# ARMBAND.net
KiCad netlist of a schematic drawn in Altium Designer
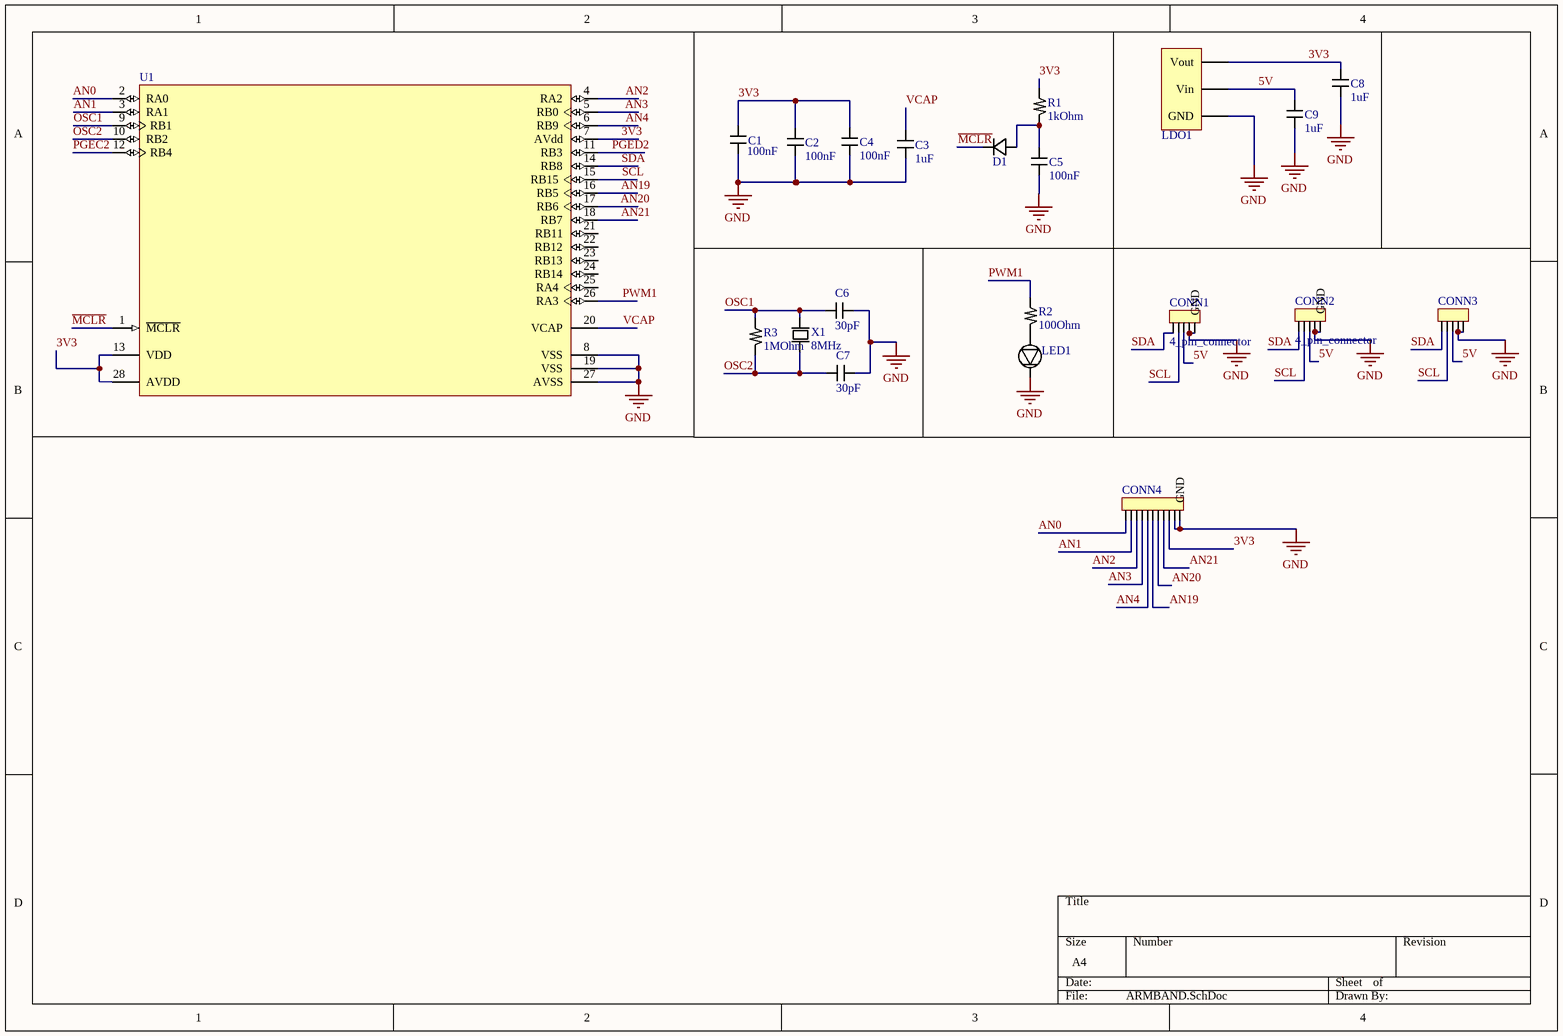
[diagram p0: ARMBAND.SchDoc]

(export (version "E")
  (design (tool "Eeschema 10.0.6"))
  (components
    (comp (ref "C1")
      (value "100nF")
      (footprint "CApacitor_1608")
      (description "SMD Capacitor")
      (libsource (lib "ARMBand_Components") (part "Capacitor_SMD"))
    )
    (comp (ref "C2")
      (value "100nF")
      (footprint "CApacitor_1608")
      (description "SMD Capacitor")
      (libsource (lib "ARMBand_Components") (part "Capacitor_SMD"))
    )
    (comp (ref "C3")
      (value "1uF")
      (footprint "Capacitor_20x12")
      (description "SMD Capacitor")
      (libsource (lib "ARMBand_Components") (part "Capacitor_SMD"))
    )
    (comp (ref "C4")
      (value "100nF")
      (footprint "CApacitor_1608")
      (description "SMD Capacitor")
      (libsource (lib "ARMBand_Components") (part "Capacitor_SMD"))
    )
    (comp (ref "C5")
      (value "100nF")
      (footprint "CApacitor_1608")
      (description "SMD Capacitor")
      (libsource (lib "ARMBand_Components") (part "Capacitor_SMD"))
    )
    (comp (ref "C6")
      (value "30pF")
      (footprint "CApacitor_1608")
      (description "SMD Capacitor")
      (libsource (lib "ARMBand_Components") (part "Capacitor_SMD"))
    )
    (comp (ref "C7")
      (value "30pF")
      (footprint "CApacitor_1608")
      (description "SMD Capacitor")
      (libsource (lib "ARMBand_Components") (part "Capacitor_SMD"))
    )
    (comp (ref "C8")
      (value "1uF")
      (footprint "Capacitor_20x12")
      (description "SMD Capacitor")
      (libsource (lib "") (part "Capacitor_SMD_1"))
    )
    (comp (ref "C9")
      (value "1uF")
      (footprint "Capacitor_20x12")
      (description "SMD Capacitor")
      (libsource (lib "") (part "Capacitor_SMD_1"))
    )
    (comp (ref "CONN1")
      (value "4_pin_connector")
      (footprint "4PIN_1MMPITCH_FFC_FCP_ZIF")
      (description "4 Pin Connector")
      (libsource (lib "") (part "4_pin_connector_1"))
    )
    (comp (ref "CONN2")
      (value "4_pin_connector")
      (footprint "4PIN_1MMPITCH_FFC_FCP_ZIF")
      (description "4 Pin Connector")
      (libsource (lib "") (part "4_pin_connector_1"))
    )
    (comp (ref "CONN3")
      (value "4_pin_connector")
      (footprint "4Pin_PICO_EZ_MATE_Header")
      (description "4 Pin Connector")
      (libsource (lib "ARMBand_Components") (part "4_pin_connector"))
    )
    (comp (ref "CONN4")
      (value "10_pin_connector")
      (footprint "10Pin_1mmpitch_FFC_FCP_ZIF")
      (description "10 Pin Connector")
      (libsource (lib "ARMBand_Components") (part "10_pin_connector"))
    )
    (comp (ref "D1")
      (value "Diode_SMD")
      (footprint "DIODE_17x38")
      (description "SMD Diode")
      (libsource (lib "ARMBand_Components") (part "Diode_SMD"))
    )
    (comp (ref "LDO1")
      (value "Voltage Reg.")
      (footprint "LDO_460x260")
      (description "LDO Voltage Regulator")
      (libsource (lib "ARMBand_Components") (part "Voltage_Regulator_3.3V"))
    )
    (comp (ref "LED1")
      (value "LED_SMD")
      (footprint "LED_1608")
      (description "SMD Blue LED")
      (libsource (lib "ARMBand_Components") (part "LED_SMD"))
    )
    (comp (ref "R1")
      (value "1kOhm")
      (footprint "Resistor_1608")
      (description "SMD Resistor")
      (libsource (lib "ARMBand_Components") (part "Resistor_SMD"))
    )
    (comp (ref "R2")
      (value "100Ohm")
      (footprint "Resistor_1608")
      (description "SMD Resistor")
      (libsource (lib "ARMBand_Components") (part "Resistor_SMD"))
    )
    (comp (ref "R3")
      (value "1MOhm")
      (footprint "Resistor_1608")
      (description "SMD Resistor")
      (libsource (lib "ARMBand_Components") (part "Resistor_SMD"))
    )
    (comp (ref "U1")
      (value "DSPIC33EP128MC202-I/SO")
      (footprint "MCHP-SOIC-SO28_N")
      (fields (field (name "MANUFACTURER") "Microchip"))
      (libsource (lib "Microchip dsPIC33E") (part "DSPIC33EP128MC202-I/SO"))
    )
    (comp (ref "X1")
      (value "8MHz")
      (footprint "xTal_150x20")
      (description "8MHz Crystal/Resonator")
      (libsource (lib "ARMBand_Components") (part "xTal_ECS_inc"))
    )
  )
  (nets
    (net (code "1") (name "/3V3") (class "Default")
      (node (ref "C1") (pin "Cap_p1") (pinfunction "Cap_p1_Cap_p1") (pintype "passive"))
      (node (ref "C2") (pin "Cap_p1") (pinfunction "Cap_p1_Cap_p1") (pintype "passive"))
      (node (ref "C4") (pin "Cap_p1") (pinfunction "Cap_p1_Cap_p1") (pintype "passive"))
      (node (ref "C8") (pin "Cap_p1") (pinfunction "Cap_p1_Cap_p1") (pintype "passive"))
      (node (ref "CONN4") (pin "9") (pinfunction "9_9") (pintype "passive"))
      (node (ref "LDO1") (pin "Vout") (pinfunction "Vout_Vout") (pintype "passive"))
      (node (ref "R1") (pin "Res_p1") (pinfunction "Res_p1_Res_p1") (pintype "passive"))
      (node (ref "U1") (pin "13") (pinfunction "VDD_13") (pintype "power_in"))
      (node (ref "U1") (pin "28") (pinfunction "AVDD_28") (pintype "power_in"))
      (node (ref "U1") (pin "7") (pinfunction "AVdd_7") (pintype "bidirectional"))
    )
    (net (code "2") (name "/5V") (class "Default")
      (node (ref "C9") (pin "Cap_p1") (pinfunction "Cap_p1_Cap_p1") (pintype "passive"))
      (node (ref "CONN1") (pin "3") (pinfunction "3_3") (pintype "passive"))
      (node (ref "CONN2") (pin "3") (pinfunction "3_3") (pintype "passive"))
      (node (ref "CONN3") (pin "3") (pinfunction "3_3") (pintype "passive"))
      (node (ref "LDO1") (pin "Vin") (pinfunction "Vin_Vin") (pintype "passive"))
    )
    (net (code "4") (name "/AN0") (class "Default")
      (node (ref "CONN4") (pin "1") (pinfunction "1_1") (pintype "passive"))
      (node (ref "U1") (pin "2") (pinfunction "RA0_2") (pintype "bidirectional"))
    )
    (net (code "5") (name "/AN1") (class "Default")
      (node (ref "CONN4") (pin "2") (pinfunction "2_2") (pintype "passive"))
      (node (ref "U1") (pin "3") (pinfunction "RA1_3") (pintype "bidirectional"))
    )
    (net (code "6") (name "/AN2") (class "Default")
      (node (ref "CONN4") (pin "3") (pinfunction "3_3") (pintype "passive"))
      (node (ref "U1") (pin "4") (pinfunction "RA2_4") (pintype "bidirectional"))
    )
    (net (code "7") (name "/AN3") (class "Default")
      (node (ref "CONN4") (pin "4") (pinfunction "4_4") (pintype "passive"))
      (node (ref "U1") (pin "5") (pinfunction "RB0_5") (pintype "bidirectional"))
    )
    (net (code "8") (name "/AN4") (class "Default")
      (node (ref "CONN4") (pin "5") (pinfunction "5_5") (pintype "passive"))
      (node (ref "U1") (pin "6") (pinfunction "RB9_6") (pintype "bidirectional"))
    )
    (net (code "9") (name "/AN19") (class "Default")
      (node (ref "CONN4") (pin "6") (pinfunction "6_6") (pintype "passive"))
      (node (ref "U1") (pin "16") (pinfunction "RB5_16") (pintype "bidirectional"))
    )
    (net (code "10") (name "/AN20") (class "Default")
      (node (ref "CONN4") (pin "7") (pinfunction "7_7") (pintype "passive"))
      (node (ref "U1") (pin "17") (pinfunction "RB6_17") (pintype "bidirectional"))
    )
    (net (code "11") (name "/AN21") (class "Default")
      (node (ref "CONN4") (pin "8") (pinfunction "8_8") (pintype "passive"))
      (node (ref "U1") (pin "18") (pinfunction "RB7_18") (pintype "bidirectional"))
    )
    (net (code "12") (name "/OSC1") (class "Default")
      (node (ref "C6") (pin "Cap_p2") (pinfunction "Cap_p2_Cap_p2") (pintype "passive"))
      (node (ref "R3") (pin "Res_p1") (pinfunction "Res_p1_Res_p1") (pintype "passive"))
      (node (ref "U1") (pin "9") (pinfunction "RB1_9") (pintype "bidirectional"))
      (node (ref "X1") (pin "xTal_0") (pinfunction "xTal_0_xTal_0") (pintype "passive"))
    )
    (net (code "13") (name "/OSC2") (class "Default")
      (node (ref "C7") (pin "Cap_p2") (pinfunction "Cap_p2_Cap_p2") (pintype "passive"))
      (node (ref "R3") (pin "Res_p2") (pinfunction "Res_p2_Res_p2") (pintype "passive"))
      (node (ref "U1") (pin "10") (pinfunction "RB2_10") (pintype "bidirectional"))
      (node (ref "X1") (pin "xTal_1") (pinfunction "xTal_1_xTal_1") (pintype "passive"))
    )
    (net (code "14") (name "/PGEC2") (class "Default")
      (node (ref "U1") (pin "12") (pinfunction "RB4_12") (pintype "bidirectional"))
    )
    (net (code "15") (name "/PGED2") (class "Default")
      (node (ref "U1") (pin "11") (pinfunction "RB3_11") (pintype "bidirectional"))
    )
    (net (code "16") (name "/PWM1") (class "Default")
      (node (ref "R2") (pin "Res_p1") (pinfunction "Res_p1_Res_p1") (pintype "passive"))
      (node (ref "U1") (pin "26") (pinfunction "RA3_26") (pintype "bidirectional"))
    )
    (net (code "17") (name "/SCL") (class "Default")
      (node (ref "CONN1") (pin "2") (pinfunction "2_2") (pintype "passive"))
      (node (ref "CONN2") (pin "2") (pinfunction "2_2") (pintype "passive"))
      (node (ref "CONN3") (pin "2") (pinfunction "2_2") (pintype "passive"))
      (node (ref "U1") (pin "15") (pinfunction "RB15_15") (pintype "bidirectional"))
    )
    (net (code "18") (name "/SDA") (class "Default")
      (node (ref "CONN1") (pin "1") (pinfunction "1_1") (pintype "passive"))
      (node (ref "CONN2") (pin "1") (pinfunction "1_1") (pintype "passive"))
      (node (ref "CONN3") (pin "1") (pinfunction "1_1") (pintype "passive"))
      (node (ref "U1") (pin "14") (pinfunction "RB8_14") (pintype "bidirectional"))
    )
    (net (code "19") (name "/VCAP") (class "Default")
      (node (ref "C3") (pin "Cap_p1") (pinfunction "Cap_p1_Cap_p1") (pintype "passive"))
      (node (ref "U1") (pin "20") (pinfunction "VCAP_20") (pintype "passive"))
    )
    (net (code "20") (name "/~{MCLR}") (class "Default")
      (node (ref "D1") (pin "Cathode") (pinfunction "Cathode_Cathode") (pintype "passive"))
      (node (ref "U1") (pin "1") (pinfunction "~{MCLR}_1") (pintype "input"))
    )
    (net (code "21") (name "GND") (class "Default")
      (node (ref "C1") (pin "Cap_p2") (pinfunction "Cap_p2_Cap_p2") (pintype "passive"))
      (node (ref "C2") (pin "Cap_p2") (pinfunction "Cap_p2_Cap_p2") (pintype "passive"))
      (node (ref "C3") (pin "Cap_p2") (pinfunction "Cap_p2_Cap_p2") (pintype "passive"))
      (node (ref "C4") (pin "Cap_p2") (pinfunction "Cap_p2_Cap_p2") (pintype "passive"))
      (node (ref "C5") (pin "Cap_p2") (pinfunction "Cap_p2_Cap_p2") (pintype "passive"))
      (node (ref "C6") (pin "Cap_p1") (pinfunction "Cap_p1_Cap_p1") (pintype "passive"))
      (node (ref "C7") (pin "Cap_p1") (pinfunction "Cap_p1_Cap_p1") (pintype "passive"))
      (node (ref "C8") (pin "Cap_p2") (pinfunction "Cap_p2_Cap_p2") (pintype "passive"))
      (node (ref "C9") (pin "Cap_p2") (pinfunction "Cap_p2_Cap_p2") (pintype "passive"))
      (node (ref "CONN1") (pin "4") (pinfunction "4_4") (pintype "passive"))
      (node (ref "CONN1") (pin "GND") (pinfunction "GND_GND") (pintype "passive"))
      (node (ref "CONN2") (pin "4") (pinfunction "4_4") (pintype "passive"))
      (node (ref "CONN2") (pin "GND") (pinfunction "GND_GND") (pintype "passive"))
      (node (ref "CONN3") (pin "4") (pinfunction "4_4") (pintype "passive"))
      (node (ref "CONN3") (pin "GND") (pinfunction "GND_GND") (pintype "passive"))
      (node (ref "CONN4") (pin "10") (pinfunction "10_10") (pintype "passive"))
      (node (ref "CONN4") (pin "GND") (pinfunction "GND_GND") (pintype "passive"))
      (node (ref "LDO1") (pin "GND") (pinfunction "GND_GND") (pintype "passive"))
      (node (ref "LED1") (pin "Cathode") (pinfunction "Cathode_Cathode") (pintype "passive"))
      (node (ref "U1") (pin "19") (pinfunction "VSS_19") (pintype "power_in"))
      (node (ref "U1") (pin "27") (pinfunction "AVSS_27") (pintype "power_in"))
      (node (ref "U1") (pin "8") (pinfunction "VSS_8") (pintype "power_in"))
    )
    (net (code "22") (name "Net-(C5-PadCap_p1)") (class "Default")
      (node (ref "C5") (pin "Cap_p1") (pinfunction "Cap_p1_Cap_p1") (pintype "passive"))
      (node (ref "D1") (pin "Anode") (pinfunction "Anode_Anode") (pintype "passive"))
      (node (ref "R1") (pin "Res_p2") (pinfunction "Res_p2_Res_p2") (pintype "passive"))
    )
    (net (code "23") (name "Net-(LED1-PadAnode)") (class "Default")
      (node (ref "LED1") (pin "Anode") (pinfunction "Anode_Anode") (pintype "passive"))
      (node (ref "R2") (pin "Res_p2") (pinfunction "Res_p2_Res_p2") (pintype "passive"))
    )
    (net (code "24") (name "unconnected-(U1-RA4-Pad25)") (class "Default")
      (node (ref "U1") (pin "25") (pinfunction "RA4_25") (pintype "bidirectional"))
    )
    (net (code "25") (name "unconnected-(U1-RB11-Pad21)") (class "Default")
      (node (ref "U1") (pin "21") (pinfunction "RB11_21") (pintype "bidirectional"))
    )
    (net (code "26") (name "unconnected-(U1-RB12-Pad22)") (class "Default")
      (node (ref "U1") (pin "22") (pinfunction "RB12_22") (pintype "bidirectional"))
    )
    (net (code "27") (name "unconnected-(U1-RB13-Pad23)") (class "Default")
      (node (ref "U1") (pin "23") (pinfunction "RB13_23") (pintype "bidirectional"))
    )
    (net (code "28") (name "unconnected-(U1-RB14-Pad24)") (class "Default")
      (node (ref "U1") (pin "24") (pinfunction "RB14_24") (pintype "bidirectional"))
    )
  )
)
